# RP2040.net
KiCad netlist of a schematic drawn in Altium Designer
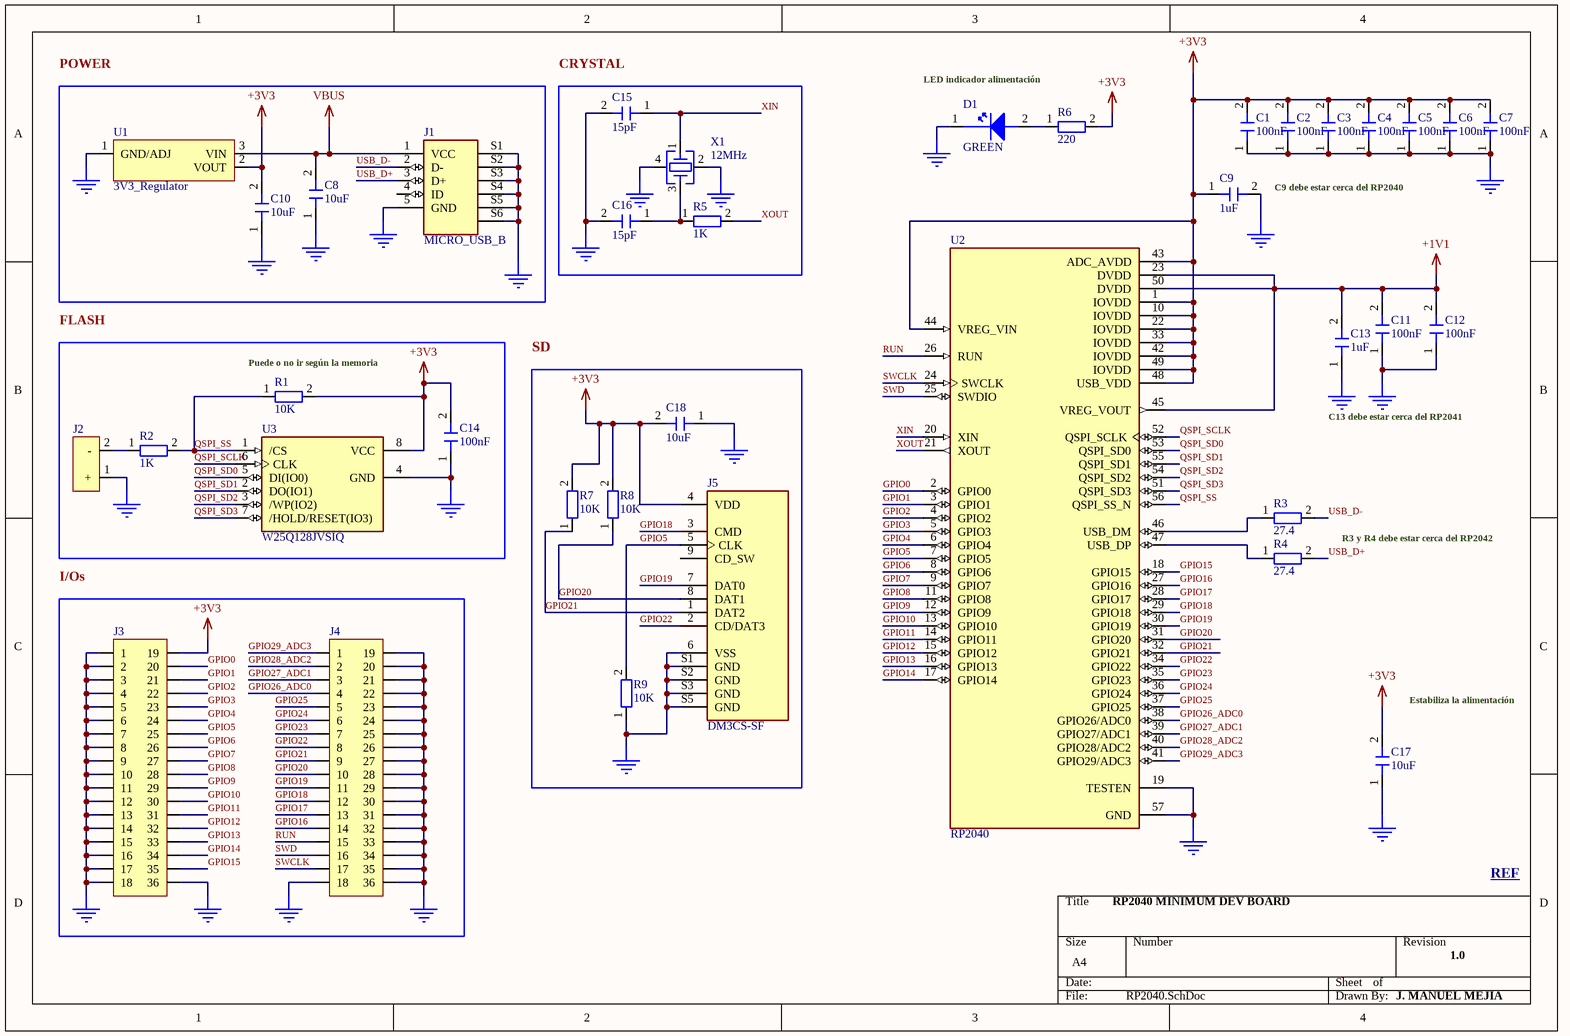
[diagram p0: RP2040.SchDoc]

(export (version "E")
  (design (tool "Eeschema 10.0.6"))
  (components
    (comp (ref "C1")
      (value "100nF")
      (footprint "C0402")
      (description "CAP CER 50V X7R 0402")
      (libsource (lib "Schlib") (part "CAP0402"))
    )
    (comp (ref "C2")
      (value "100nF")
      (footprint "C0402")
      (description "CAP CER 50V X7R 0402")
      (libsource (lib "Schlib") (part "CAP0402"))
    )
    (comp (ref "C3")
      (value "100nF")
      (footprint "C0402")
      (description "CAP CER 50V X7R 0402")
      (libsource (lib "Schlib") (part "CAP0402"))
    )
    (comp (ref "C4")
      (value "100nF")
      (footprint "C0402")
      (description "CAP CER 50V X7R 0402")
      (libsource (lib "Schlib") (part "CAP0402"))
    )
    (comp (ref "C5")
      (value "100nF")
      (footprint "C0402")
      (description "CAP CER 50V X7R 0402")
      (libsource (lib "Schlib") (part "CAP0402"))
    )
    (comp (ref "C6")
      (value "100nF")
      (footprint "C0402")
      (description "CAP CER 50V X7R 0402")
      (libsource (lib "Schlib") (part "CAP0402"))
    )
    (comp (ref "C7")
      (value "100nF")
      (footprint "C0402")
      (description "CAP CER 50V X7R 0402")
      (libsource (lib "Schlib") (part "CAP0402"))
    )
    (comp (ref "C8")
      (value "10uF")
      (footprint "C0603")
      (description "CAP CER 50V X7R 0603")
      (libsource (lib "Schlib") (part "CAP0603"))
    )
    (comp (ref "C9")
      (value "1uF")
      (footprint "C0402")
      (description "CAP CER 50V X7R 0402")
      (libsource (lib "Schlib") (part "CAP0402"))
    )
    (comp (ref "C10")
      (value "10uF")
      (footprint "C0603")
      (description "CAP CER 50V X7R 0603")
      (libsource (lib "Schlib") (part "CAP0603"))
    )
    (comp (ref "C11")
      (value "100nF")
      (footprint "C0402")
      (description "CAP CER 50V X7R 0402")
      (libsource (lib "Schlib") (part "CAP0402"))
    )
    (comp (ref "C12")
      (value "100nF")
      (footprint "C0402")
      (description "CAP CER 50V X7R 0402")
      (libsource (lib "Schlib") (part "CAP0402"))
    )
    (comp (ref "C13")
      (value "1uF")
      (footprint "C0402")
      (description "CAP CER 50V X7R 0402")
      (libsource (lib "Schlib") (part "CAP0402"))
    )
    (comp (ref "C14")
      (value "100nF")
      (footprint "C0402")
      (description "CAP CER 50V X7R 0402")
      (libsource (lib "Schlib") (part "CAP0402"))
    )
    (comp (ref "C15")
      (value "15pF")
      (footprint "C0402")
      (description "CAP CER 50V X7R 0402")
      (libsource (lib "Schlib") (part "CAP0402"))
    )
    (comp (ref "C16")
      (value "15pF")
      (footprint "C0402")
      (description "CAP CER 50V X7R 0402")
      (libsource (lib "Schlib") (part "CAP0402"))
    )
    (comp (ref "C17")
      (value "10uF")
      (footprint "C0603")
      (description "CAP CER 50V X7R 0603")
      (libsource (lib "Schlib") (part "CAP0603"))
    )
    (comp (ref "C18")
      (value "10uF")
      (footprint "C0603")
      (description "CAP CER 50V X7R 0603")
      (libsource (lib "Schlib") (part "CAP0603"))
    )
    (comp (ref "D1")
      (value "GREEN")
      (footprint "LED0603_GREEN")
      (description "LED GREEN CLEAR CHIP 0603 SMD")
      (fields
        (field (name "MANUFACTURER") "Visual Communications")
        (field (name "MANUFACTURER PART NUMBER") "LSM0603453V")
      )
      (libsource (lib "Schlib") (part "LED0603"))
    )
    (comp (ref "J1")
      (value "MICRO_USB_B")
      (footprint "MICRO_USB_B")
      (description "CONN RCPT USB2.0 MICRO B SMD R/A")
      (libsource (lib "Schlib") (part "MICRO_USB_B"))
    )
    (comp (ref "J2")
      (value "1x2 HEADER")
      (footprint "HEADER1X2")
      (description "CONN HEADER VERT 2POS 2.54MM")
      (fields (field (name "MANUFACTURER") "Molex") (field (name "MANUFACTURER PART NUMBER") "22-27-2021"))
      (libsource (lib "Schlib") (part "22-27-2021"))
    )
    (comp (ref "J3")
      (value "2X18 HEADER")
      (footprint "2X18 HEADER")
      (description "2X18 2.54 MALE HEADER")
      (libsource (lib "Schlib") (part "2X18 HEADER"))
    )
    (comp (ref "J4")
      (value "2X18 HEADER")
      (footprint "2X18 HEADER")
      (description "2X18 2.54 MALE HEADER")
      (libsource (lib "Schlib") (part "2X18 HEADER"))
    )
    (comp (ref "J5")
      (value "DM3CS-SF")
      (footprint "DM3CS-SF")
      (description "Connector, Memory, Micro Sd, Hinged Rohs Compliant: Yes ¦Hirose(Hrs) DM3CS-SF")
      (fields (field (name "MANUFACTURER") "Hirose"))
      (libsource (lib "Schlib") (part "DM3CS-SF"))
    )
    (comp (ref "R1")
      (value "10K")
      (footprint "R0402")
      (description "RES 5% 1/16W 0402")
      (libsource (lib "Schlib") (part "RES0402"))
    )
    (comp (ref "R2")
      (value "1K")
      (footprint "R0402")
      (description "RES 5% 1/16W 0402")
      (libsource (lib "Schlib") (part "RES0402"))
    )
    (comp (ref "R3")
      (value "27.4")
      (footprint "R0402")
      (description "RES 5% 1/16W 0402")
      (libsource (lib "Schlib") (part "RES0402"))
    )
    (comp (ref "R4")
      (value "27.4")
      (footprint "R0402")
      (description "RES 5% 1/16W 0402")
      (libsource (lib "Schlib") (part "RES0402"))
    )
    (comp (ref "R5")
      (value "1K")
      (footprint "R0402")
      (description "RES 5% 1/16W 0402")
      (libsource (lib "Schlib") (part "RES0402"))
    )
    (comp (ref "R6")
      (value "220")
      (footprint "R0402")
      (description "RES 5% 1/16W 0402")
      (libsource (lib "Schlib") (part "RES0402"))
    )
    (comp (ref "R7")
      (value "10K")
      (footprint "R0402")
      (description "RES 5% 1/16W 0402")
      (libsource (lib "Schlib") (part "RES0402"))
    )
    (comp (ref "R8")
      (value "10K")
      (footprint "R0402")
      (description "RES 5% 1/16W 0402")
      (libsource (lib "Schlib") (part "RES0402"))
    )
    (comp (ref "R9")
      (value "10K")
      (footprint "R0402")
      (description "RES 5% 1/16W 0402")
      (libsource (lib "Schlib") (part "RES0402"))
    )
    (comp (ref "U1")
      (value "3V3_Regulator")
      (footprint "3V3_SOT223")
      (description "IC REG LINEAR 3.3V 1A SOT223")
      (libsource (lib "Schlib") (part "3V3_Regulator"))
    )
    (comp (ref "U2")
      (value "RP2040")
      (footprint "RP2040")
      (description "IC MCU 32BIT EXT MEM 56QFN")
      (fields (field (name "MF") "Raspberry Pi") (field (name "MP") "SC0914(13)"))
      (libsource (lib "Schlib") (part "RP2040"))
    )
    (comp (ref "U3")
      (value "W25Q128JVSIQ")
      (footprint "W25Q128JVSIQ")
      (description "IC FLASH 128MBIT SPI/QUAD 8SOIC")
      (fields (field (name "MANUFACTURER") "Winbond"))
      (libsource (lib "Schlib") (part "W25Q128JVSIQ"))
    )
    (comp (ref "X1")
      (value "12MHz")
      (footprint "ABM8G")
      (description "CRYSTAL 12.0000MHZ 10PF SMD")
      (libsource (lib "Schlib") (part "ABM8G"))
    )
  )
  (nets
    (net (code "1") (name "+1V1") (class "Default")
      (node (ref "C11") (pin "2") (pinfunction "2_2") (pintype "passive"))
      (node (ref "C12") (pin "2") (pinfunction "2_2") (pintype "passive"))
      (node (ref "C13") (pin "2") (pinfunction "2_2") (pintype "passive"))
      (node (ref "U2") (pin "23") (pinfunction "DVDD_23") (pintype "power_in"))
      (node (ref "U2") (pin "45") (pinfunction "VREG_VOUT_45") (pintype "output"))
      (node (ref "U2") (pin "50") (pinfunction "DVDD_50") (pintype "power_in"))
    )
    (net (code "2") (name "+3V3") (class "Default")
      (node (ref "C1") (pin "2") (pinfunction "2_2") (pintype "passive"))
      (node (ref "C10") (pin "2") (pinfunction "2_2") (pintype "passive"))
      (node (ref "C14") (pin "2") (pinfunction "2_2") (pintype "passive"))
      (node (ref "C17") (pin "2") (pinfunction "2_2") (pintype "passive"))
      (node (ref "C18") (pin "2") (pinfunction "2_2") (pintype "passive"))
      (node (ref "C2") (pin "2") (pinfunction "2_2") (pintype "passive"))
      (node (ref "C3") (pin "2") (pinfunction "2_2") (pintype "passive"))
      (node (ref "C4") (pin "2") (pinfunction "2_2") (pintype "passive"))
      (node (ref "C5") (pin "2") (pinfunction "2_2") (pintype "passive"))
      (node (ref "C6") (pin "2") (pinfunction "2_2") (pintype "passive"))
      (node (ref "C7") (pin "2") (pinfunction "2_2") (pintype "passive"))
      (node (ref "C9") (pin "1") (pinfunction "1_1") (pintype "passive"))
      (node (ref "J3") (pin "19") (pinfunction "19_19") (pintype "passive"))
      (node (ref "J5") (pin "4") (pinfunction "VDD_4") (pintype "passive"))
      (node (ref "R1") (pin "2") (pinfunction "2_2") (pintype "passive"))
      (node (ref "R6") (pin "2") (pinfunction "2_2") (pintype "passive"))
      (node (ref "R7") (pin "2") (pinfunction "2_2") (pintype "passive"))
      (node (ref "R8") (pin "2") (pinfunction "2_2") (pintype "passive"))
      (node (ref "U1") (pin "2") (pinfunction "VOUT_2") (pintype "passive"))
      (node (ref "U2") (pin "1") (pinfunction "IOVDD_1") (pintype "power_in"))
      (node (ref "U2") (pin "10") (pinfunction "IOVDD_10") (pintype "power_in"))
      (node (ref "U2") (pin "22") (pinfunction "IOVDD_22") (pintype "power_in"))
      (node (ref "U2") (pin "33") (pinfunction "IOVDD_33") (pintype "power_in"))
      (node (ref "U2") (pin "42") (pinfunction "IOVDD_42") (pintype "power_in"))
      (node (ref "U2") (pin "43") (pinfunction "ADC_AVDD_43") (pintype "power_in"))
      (node (ref "U2") (pin "44") (pinfunction "VREG_VIN_44") (pintype "input"))
      (node (ref "U2") (pin "48") (pinfunction "USB_VDD_48") (pintype "power_in"))
      (node (ref "U2") (pin "49") (pinfunction "IOVDD_49") (pintype "power_in"))
      (node (ref "U3") (pin "8") (pinfunction "VCC_8") (pintype "power_in"))
    )
    (net (code "3") (name "/GPIO0") (class "Default")
      (node (ref "J3") (pin "20") (pinfunction "20_20") (pintype "passive"))
      (node (ref "U2") (pin "2") (pinfunction "GPIO0_2") (pintype "bidirectional"))
    )
    (net (code "4") (name "/GPIO1") (class "Default")
      (node (ref "J3") (pin "21") (pinfunction "21_21") (pintype "passive"))
      (node (ref "U2") (pin "3") (pinfunction "GPIO1_3") (pintype "bidirectional"))
    )
    (net (code "5") (name "/GPIO2") (class "Default")
      (node (ref "J3") (pin "22") (pinfunction "22_22") (pintype "passive"))
      (node (ref "U2") (pin "4") (pinfunction "GPIO2_4") (pintype "bidirectional"))
    )
    (net (code "6") (name "/GPIO3") (class "Default")
      (node (ref "J3") (pin "23") (pinfunction "23_23") (pintype "passive"))
      (node (ref "U2") (pin "5") (pinfunction "GPIO3_5") (pintype "bidirectional"))
    )
    (net (code "7") (name "/GPIO4") (class "Default")
      (node (ref "J3") (pin "24") (pinfunction "24_24") (pintype "passive"))
      (node (ref "U2") (pin "6") (pinfunction "GPIO4_6") (pintype "bidirectional"))
    )
    (net (code "8") (name "/GPIO5") (class "Default")
      (node (ref "J3") (pin "25") (pinfunction "25_25") (pintype "passive"))
      (node (ref "J5") (pin "5") (pinfunction "CLK_5") (pintype "passive"))
      (node (ref "R9") (pin "2") (pinfunction "2_2") (pintype "passive"))
      (node (ref "U2") (pin "7") (pinfunction "GPIO5_7") (pintype "bidirectional"))
    )
    (net (code "9") (name "/GPIO6") (class "Default")
      (node (ref "J3") (pin "26") (pinfunction "26_26") (pintype "passive"))
      (node (ref "U2") (pin "8") (pinfunction "GPIO6_8") (pintype "bidirectional"))
    )
    (net (code "10") (name "/GPIO7") (class "Default")
      (node (ref "J3") (pin "27") (pinfunction "27_27") (pintype "passive"))
      (node (ref "U2") (pin "9") (pinfunction "GPIO7_9") (pintype "bidirectional"))
    )
    (net (code "11") (name "/GPIO8") (class "Default")
      (node (ref "J3") (pin "28") (pinfunction "28_28") (pintype "passive"))
      (node (ref "U2") (pin "11") (pinfunction "GPIO8_11") (pintype "bidirectional"))
    )
    (net (code "12") (name "/GPIO9") (class "Default")
      (node (ref "J3") (pin "29") (pinfunction "29_29") (pintype "passive"))
      (node (ref "U2") (pin "12") (pinfunction "GPIO9_12") (pintype "bidirectional"))
    )
    (net (code "13") (name "/GPIO10") (class "Default")
      (node (ref "J3") (pin "30") (pinfunction "30_30") (pintype "passive"))
      (node (ref "U2") (pin "13") (pinfunction "GPIO10_13") (pintype "bidirectional"))
    )
    (net (code "14") (name "/GPIO11") (class "Default")
      (node (ref "J3") (pin "31") (pinfunction "31_31") (pintype "passive"))
      (node (ref "U2") (pin "14") (pinfunction "GPIO11_14") (pintype "bidirectional"))
    )
    (net (code "15") (name "/GPIO12") (class "Default")
      (node (ref "J3") (pin "32") (pinfunction "32_32") (pintype "passive"))
      (node (ref "U2") (pin "15") (pinfunction "GPIO12_15") (pintype "bidirectional"))
    )
    (net (code "16") (name "/GPIO13") (class "Default")
      (node (ref "J3") (pin "33") (pinfunction "33_33") (pintype "passive"))
      (node (ref "U2") (pin "16") (pinfunction "GPIO13_16") (pintype "bidirectional"))
    )
    (net (code "17") (name "/GPIO14") (class "Default")
      (node (ref "J3") (pin "34") (pinfunction "34_34") (pintype "passive"))
      (node (ref "U2") (pin "17") (pinfunction "GPIO14_17") (pintype "bidirectional"))
    )
    (net (code "18") (name "/GPIO15") (class "Default")
      (node (ref "J3") (pin "35") (pinfunction "35_35") (pintype "passive"))
      (node (ref "U2") (pin "18") (pinfunction "GPIO15_18") (pintype "bidirectional"))
    )
    (net (code "19") (name "/GPIO16") (class "Default")
      (node (ref "J4") (pin "14") (pinfunction "14_14") (pintype "passive"))
      (node (ref "U2") (pin "27") (pinfunction "GPIO16_27") (pintype "bidirectional"))
    )
    (net (code "20") (name "/GPIO17") (class "Default")
      (node (ref "J4") (pin "13") (pinfunction "13_13") (pintype "passive"))
      (node (ref "U2") (pin "28") (pinfunction "GPIO17_28") (pintype "bidirectional"))
    )
    (net (code "21") (name "/GPIO18") (class "Default")
      (node (ref "J4") (pin "12") (pinfunction "12_12") (pintype "passive"))
      (node (ref "J5") (pin "3") (pinfunction "CMD_3") (pintype "passive"))
      (node (ref "U2") (pin "29") (pinfunction "GPIO18_29") (pintype "bidirectional"))
    )
    (net (code "22") (name "/GPIO19") (class "Default")
      (node (ref "J4") (pin "11") (pinfunction "11_11") (pintype "passive"))
      (node (ref "J5") (pin "7") (pinfunction "DAT0_7") (pintype "passive"))
      (node (ref "U2") (pin "30") (pinfunction "GPIO19_30") (pintype "bidirectional"))
    )
    (net (code "23") (name "/GPIO20") (class "Default")
      (node (ref "J4") (pin "10") (pinfunction "10_10") (pintype "passive"))
      (node (ref "J5") (pin "8") (pinfunction "DAT1_8") (pintype "passive"))
      (node (ref "R8") (pin "1") (pinfunction "1_1") (pintype "passive"))
      (node (ref "U2") (pin "31") (pinfunction "GPIO20_31") (pintype "bidirectional"))
    )
    (net (code "24") (name "/GPIO21") (class "Default")
      (node (ref "J4") (pin "9") (pinfunction "9_9") (pintype "passive"))
      (node (ref "J5") (pin "1") (pinfunction "DAT2_1") (pintype "passive"))
      (node (ref "R7") (pin "1") (pinfunction "1_1") (pintype "passive"))
      (node (ref "U2") (pin "32") (pinfunction "GPIO21_32") (pintype "bidirectional"))
    )
    (net (code "25") (name "/GPIO22") (class "Default")
      (node (ref "J4") (pin "8") (pinfunction "8_8") (pintype "passive"))
      (node (ref "J5") (pin "2") (pinfunction "CD/DAT3_2") (pintype "passive"))
      (node (ref "U2") (pin "34") (pinfunction "GPIO22_34") (pintype "bidirectional"))
    )
    (net (code "26") (name "/GPIO23") (class "Default")
      (node (ref "J4") (pin "7") (pinfunction "7_7") (pintype "passive"))
      (node (ref "U2") (pin "35") (pinfunction "GPIO23_35") (pintype "bidirectional"))
    )
    (net (code "27") (name "/GPIO24") (class "Default")
      (node (ref "J4") (pin "6") (pinfunction "6_6") (pintype "passive"))
      (node (ref "U2") (pin "36") (pinfunction "GPIO24_36") (pintype "bidirectional"))
    )
    (net (code "28") (name "/GPIO25") (class "Default")
      (node (ref "J4") (pin "5") (pinfunction "5_5") (pintype "passive"))
      (node (ref "U2") (pin "37") (pinfunction "GPIO25_37") (pintype "bidirectional"))
    )
    (net (code "29") (name "/GPIO26_ADC0") (class "Default")
      (node (ref "J4") (pin "4") (pinfunction "4_4") (pintype "passive"))
      (node (ref "U2") (pin "38") (pinfunction "GPIO26/ADC0_38") (pintype "bidirectional"))
    )
    (net (code "30") (name "/GPIO27_ADC1") (class "Default")
      (node (ref "J4") (pin "3") (pinfunction "3_3") (pintype "passive"))
      (node (ref "U2") (pin "39") (pinfunction "GPIO27/ADC1_39") (pintype "bidirectional"))
    )
    (net (code "31") (name "/GPIO28_ADC2") (class "Default")
      (node (ref "J4") (pin "2") (pinfunction "2_2") (pintype "passive"))
      (node (ref "U2") (pin "40") (pinfunction "GPIO28/ADC2_40") (pintype "bidirectional"))
    )
    (net (code "32") (name "/GPIO29_ADC3") (class "Default")
      (node (ref "J4") (pin "1") (pinfunction "1_1") (pintype "passive"))
      (node (ref "U2") (pin "41") (pinfunction "GPIO29/ADC3_41") (pintype "bidirectional"))
    )
    (net (code "33") (name "/QSPI_SCLK") (class "Default")
      (node (ref "U2") (pin "52") (pinfunction "QSPI_SCLK_52") (pintype "bidirectional"))
      (node (ref "U3") (pin "6") (pinfunction "CLK_6") (pintype "input"))
    )
    (net (code "34") (name "/QSPI_SD0") (class "Default")
      (node (ref "U2") (pin "53") (pinfunction "QSPI_SD0_53") (pintype "bidirectional"))
      (node (ref "U3") (pin "5") (pinfunction "DI(IO0)_5") (pintype "bidirectional"))
    )
    (net (code "35") (name "/QSPI_SD1") (class "Default")
      (node (ref "U2") (pin "55") (pinfunction "QSPI_SD1_55") (pintype "bidirectional"))
      (node (ref "U3") (pin "2") (pinfunction "DO(IO1)_2") (pintype "bidirectional"))
    )
    (net (code "36") (name "/QSPI_SD2") (class "Default")
      (node (ref "U2") (pin "54") (pinfunction "QSPI_SD2_54") (pintype "bidirectional"))
      (node (ref "U3") (pin "3") (pinfunction "/WP(IO2)_3") (pintype "bidirectional"))
    )
    (net (code "37") (name "/QSPI_SD3") (class "Default")
      (node (ref "U2") (pin "51") (pinfunction "QSPI_SD3_51") (pintype "bidirectional"))
      (node (ref "U3") (pin "7") (pinfunction "/HOLD/RESET(IO3)_7") (pintype "bidirectional"))
    )
    (net (code "38") (name "/QSPI_SS") (class "Default")
      (node (ref "R1") (pin "1") (pinfunction "1_1") (pintype "passive"))
      (node (ref "R2") (pin "2") (pinfunction "2_2") (pintype "passive"))
      (node (ref "U2") (pin "56") (pinfunction "QSPI_SS_N_56") (pintype "bidirectional"))
      (node (ref "U3") (pin "1") (pinfunction "/CS_1") (pintype "input"))
    )
    (net (code "39") (name "/RUN") (class "Default")
      (node (ref "J4") (pin "15") (pinfunction "15_15") (pintype "passive"))
      (node (ref "U2") (pin "26") (pinfunction "RUN_26") (pintype "input"))
    )
    (net (code "40") (name "/SWCLK") (class "Default")
      (node (ref "J4") (pin "17") (pinfunction "17_17") (pintype "passive"))
      (node (ref "U2") (pin "24") (pinfunction "SWCLK_24") (pintype "input"))
    )
    (net (code "41") (name "/SWD") (class "Default")
      (node (ref "J4") (pin "16") (pinfunction "16_16") (pintype "passive"))
      (node (ref "U2") (pin "25") (pinfunction "SWDIO_25") (pintype "bidirectional"))
    )
    (net (code "42") (name "/USB_D+") (class "Default")
      (node (ref "J1") (pin "3") (pinfunction "D+_3") (pintype "bidirectional"))
      (node (ref "R4") (pin "2") (pinfunction "2_2") (pintype "passive"))
    )
    (net (code "43") (name "/USB_D-") (class "Default")
      (node (ref "J1") (pin "2") (pinfunction "D-_2") (pintype "bidirectional"))
      (node (ref "R3") (pin "2") (pinfunction "2_2") (pintype "passive"))
    )
    (net (code "44") (name "/XIN") (class "Default")
      (node (ref "C15") (pin "1") (pinfunction "1_1") (pintype "passive"))
      (node (ref "U2") (pin "20") (pinfunction "XIN_20") (pintype "input"))
      (node (ref "X1") (pin "1") (pinfunction "1_1") (pintype "passive"))
    )
    (net (code "45") (name "/XOUT") (class "Default")
      (node (ref "R5") (pin "2") (pinfunction "2_2") (pintype "passive"))
      (node (ref "U2") (pin "21") (pinfunction "XOUT_21") (pintype "output"))
    )
    (net (code "46") (name "GND") (class "Default")
      (node (ref "C1") (pin "1") (pinfunction "1_1") (pintype "passive"))
      (node (ref "C10") (pin "1") (pinfunction "1_1") (pintype "passive"))
      (node (ref "C11") (pin "1") (pinfunction "1_1") (pintype "passive"))
      (node (ref "C12") (pin "1") (pinfunction "1_1") (pintype "passive"))
      (node (ref "C13") (pin "1") (pinfunction "1_1") (pintype "passive"))
      (node (ref "C14") (pin "1") (pinfunction "1_1") (pintype "passive"))
      (node (ref "C15") (pin "2") (pinfunction "2_2") (pintype "passive"))
      (node (ref "C16") (pin "2") (pinfunction "2_2") (pintype "passive"))
      (node (ref "C17") (pin "1") (pinfunction "1_1") (pintype "passive"))
      (node (ref "C18") (pin "1") (pinfunction "1_1") (pintype "passive"))
      (node (ref "C2") (pin "1") (pinfunction "1_1") (pintype "passive"))
      (node (ref "C3") (pin "1") (pinfunction "1_1") (pintype "passive"))
      (node (ref "C4") (pin "1") (pinfunction "1_1") (pintype "passive"))
      (node (ref "C5") (pin "1") (pinfunction "1_1") (pintype "passive"))
      (node (ref "C6") (pin "1") (pinfunction "1_1") (pintype "passive"))
      (node (ref "C7") (pin "1") (pinfunction "1_1") (pintype "passive"))
      (node (ref "C8") (pin "1") (pinfunction "1_1") (pintype "passive"))
      (node (ref "C9") (pin "2") (pinfunction "2_2") (pintype "passive"))
      (node (ref "D1") (pin "1") (pinfunction "1_1") (pintype "passive"))
      (node (ref "J1") (pin "5") (pinfunction "GND_5") (pintype "power_in"))
      (node (ref "J1") (pin "S1") (pinfunction "SHIELD_S1") (pintype "passive"))
      (node (ref "J1") (pin "S2") (pinfunction "SHIELD_S2") (pintype "passive"))
      (node (ref "J1") (pin "S3") (pinfunction "SHIELD_S3") (pintype "passive"))
      (node (ref "J1") (pin "S4") (pinfunction "SHIELD_S4") (pintype "passive"))
      (node (ref "J1") (pin "S5") (pinfunction "SHIELD_S5") (pintype "passive"))
      (node (ref "J1") (pin "S6") (pinfunction "SHIELD_S6") (pintype "passive"))
      (node (ref "J2") (pin "1") (pinfunction "+_1") (pintype "passive"))
      (node (ref "J3") (pin "1") (pinfunction "1_1") (pintype "passive"))
      (node (ref "J3") (pin "10") (pinfunction "10_10") (pintype "passive"))
      (node (ref "J3") (pin "11") (pinfunction "11_11") (pintype "passive"))
      (node (ref "J3") (pin "12") (pinfunction "12_12") (pintype "passive"))
      (node (ref "J3") (pin "13") (pinfunction "13_13") (pintype "passive"))
      (node (ref "J3") (pin "14") (pinfunction "14_14") (pintype "passive"))
      (node (ref "J3") (pin "15") (pinfunction "15_15") (pintype "passive"))
      (node (ref "J3") (pin "16") (pinfunction "16_16") (pintype "passive"))
      (node (ref "J3") (pin "17") (pinfunction "17_17") (pintype "passive"))
      (node (ref "J3") (pin "18") (pinfunction "18_18") (pintype "passive"))
      (node (ref "J3") (pin "2") (pinfunction "2_2") (pintype "passive"))
      (node (ref "J3") (pin "3") (pinfunction "3_3") (pintype "passive"))
      (node (ref "J3") (pin "36") (pinfunction "36_36") (pintype "passive"))
      (node (ref "J3") (pin "4") (pinfunction "4_4") (pintype "passive"))
      (node (ref "J3") (pin "5") (pinfunction "5_5") (pintype "passive"))
      (node (ref "J3") (pin "6") (pinfunction "6_6") (pintype "passive"))
      (node (ref "J3") (pin "7") (pinfunction "7_7") (pintype "passive"))
      (node (ref "J3") (pin "8") (pinfunction "8_8") (pintype "passive"))
      (node (ref "J3") (pin "9") (pinfunction "9_9") (pintype "passive"))
      (node (ref "J4") (pin "18") (pinfunction "18_18") (pintype "passive"))
      (node (ref "J4") (pin "19") (pinfunction "19_19") (pintype "passive"))
      (node (ref "J4") (pin "20") (pinfunction "20_20") (pintype "passive"))
      (node (ref "J4") (pin "21") (pinfunction "21_21") (pintype "passive"))
      (node (ref "J4") (pin "22") (pinfunction "22_22") (pintype "passive"))
      (node (ref "J4") (pin "23") (pinfunction "23_23") (pintype "passive"))
      (node (ref "J4") (pin "24") (pinfunction "24_24") (pintype "passive"))
      (node (ref "J4") (pin "25") (pinfunction "25_25") (pintype "passive"))
      (node (ref "J4") (pin "26") (pinfunction "26_26") (pintype "passive"))
      (node (ref "J4") (pin "27") (pinfunction "27_27") (pintype "passive"))
      (node (ref "J4") (pin "28") (pinfunction "28_28") (pintype "passive"))
      (node (ref "J4") (pin "29") (pinfunction "29_29") (pintype "passive"))
      (node (ref "J4") (pin "30") (pinfunction "30_30") (pintype "passive"))
      (node (ref "J4") (pin "31") (pinfunction "31_31") (pintype "passive"))
      (node (ref "J4") (pin "32") (pinfunction "32_32") (pintype "passive"))
      (node (ref "J4") (pin "33") (pinfunction "33_33") (pintype "passive"))
      (node (ref "J4") (pin "34") (pinfunction "34_34") (pintype "passive"))
      (node (ref "J4") (pin "35") (pinfunction "35_35") (pintype "passive"))
      (node (ref "J4") (pin "36") (pinfunction "36_36") (pintype "passive"))
      (node (ref "J5") (pin "6") (pinfunction "VSS_6") (pintype "passive"))
      (node (ref "J5") (pin "S1") (pinfunction "GND_S1") (pintype "passive"))
      (node (ref "J5") (pin "S2") (pinfunction "GND_S2") (pintype "passive"))
      (node (ref "J5") (pin "S3") (pinfunction "GND_S3") (pintype "passive"))
      (node (ref "J5") (pin "S5") (pinfunction "GND_S5") (pintype "passive"))
      (node (ref "R9") (pin "1") (pinfunction "1_1") (pintype "passive"))
      (node (ref "U1") (pin "1") (pinfunction "GND/ADJ_1") (pintype "passive"))
      (node (ref "U2") (pin "19") (pinfunction "TESTEN_19") (pintype "passive"))
      (node (ref "U2") (pin "57") (pinfunction "GND_57") (pintype "power_in"))
      (node (ref "U3") (pin "4") (pinfunction "GND_4") (pintype "power_in"))
      (node (ref "X1") (pin "2") (pinfunction "2_2") (pintype "passive"))
      (node (ref "X1") (pin "4") (pinfunction "4_4") (pintype "passive"))
    )
    (net (code "47") (name "Net-(C16-Pad1)") (class "Default")
      (node (ref "C16") (pin "1") (pinfunction "1_1") (pintype "passive"))
      (node (ref "R5") (pin "1") (pinfunction "1_1") (pintype "passive"))
      (node (ref "X1") (pin "3") (pinfunction "3_3") (pintype "passive"))
    )
    (net (code "48") (name "Net-(D1-Pad2)") (class "Default")
      (node (ref "D1") (pin "2") (pinfunction "2_2") (pintype "passive"))
      (node (ref "R6") (pin "1") (pinfunction "1_1") (pintype "passive"))
    )
    (net (code "49") (name "Net-(J2--)") (class "Default")
      (node (ref "J2") (pin "2") (pinfunction "-_2") (pintype "passive"))
      (node (ref "R2") (pin "1") (pinfunction "1_1") (pintype "passive"))
    )
    (net (code "50") (name "Net-(U2-USB_DM)") (class "Default")
      (node (ref "R3") (pin "1") (pinfunction "1_1") (pintype "passive"))
      (node (ref "U2") (pin "46") (pinfunction "USB_DM_46") (pintype "bidirectional"))
    )
    (net (code "51") (name "Net-(U2-USB_DP)") (class "Default")
      (node (ref "R4") (pin "1") (pinfunction "1_1") (pintype "passive"))
      (node (ref "U2") (pin "47") (pinfunction "USB_DP_47") (pintype "bidirectional"))
    )
    (net (code "52") (name "VBUS") (class "Default")
      (node (ref "C8") (pin "2") (pinfunction "2_2") (pintype "passive"))
      (node (ref "J1") (pin "1") (pinfunction "VCC_1") (pintype "power_in"))
      (node (ref "U1") (pin "3") (pinfunction "VIN_3") (pintype "passive"))
    )
    (net (code "53") (name "unconnected-(J1-ID-Pad4)") (class "Default")
      (node (ref "J1") (pin "4") (pinfunction "ID_4") (pintype "bidirectional"))
    )
    (net (code "54") (name "unconnected-(J5-CD_SW-Pad9)") (class "Default")
      (node (ref "J5") (pin "9") (pinfunction "CD_SW_9") (pintype "passive"))
    )
  )
)
